# TO-56_Laser_Simple_4_Pin_Mount.net
KiCad netlist of a schematic drawn in EasyEDA Pro
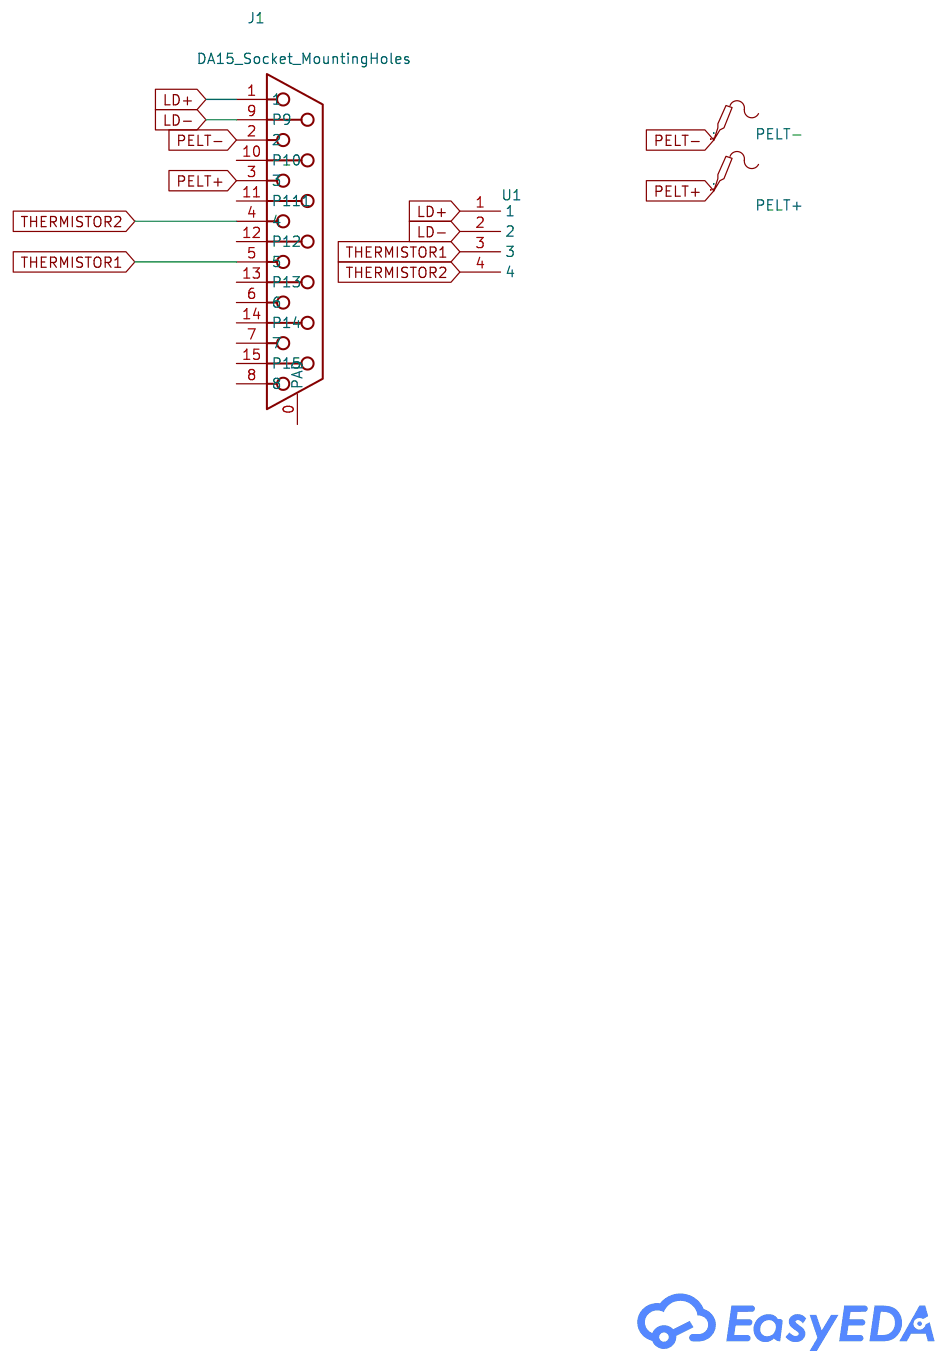
[diagram p0: schematic sheet]

(export (version "E")
  (design (tool "Eeschema 10.0.6"))
  (components
    (comp (ref "J1")
      (value "DA15_Socket_MountingHoles")
      (footprint "easyedapro:Connector_Dsub:DSUB-15_Socket_Vertical_P2.77x2.84mm_MountingHoles")
      (description "15-pin D-SUB connector, socket (female) (low-density/2 columns), Mounting Hole")
      (libsource (lib "easyedapro") (part "Connector_DA15_Socket_MountingHoles"))
    )
    (comp (ref "PELT+")
      (value "~")
      (footprint "easyedapro:Test-Point-0.5mm")
      (description "Test-Point")
      (libsource (lib "easyedapro") (part "Test-Point"))
    )
    (comp (ref "PELT-")
      (value "~")
      (footprint "easyedapro:Test-Point-0.5mm")
      (description "Test-Point")
      (libsource (lib "easyedapro") (part "Test-Point"))
    )
    (comp (ref "U1") (value "~") (footprint "easyedapro:TO56") (libsource (lib "easyedapro") (part "TO56")))
  )
  (nets
    (net (code "1") (name "LD+") (class "Default")
      (node (ref "J1") (pin "1") (pinfunction "1_1") (pintype "unspecified"))
      (node (ref "U1") (pin "1") (pinfunction "1_1") (pintype "input"))
    )
    (net (code "2") (name "LD-") (class "Default")
      (node (ref "J1") (pin "9") (pinfunction "P9_9") (pintype "unspecified"))
      (node (ref "U1") (pin "2") (pinfunction "2_2") (pintype "input"))
    )
    (net (code "3") (name "PELT+") (class "Default")
      (node (ref "J1") (pin "3") (pinfunction "3_3") (pintype "unspecified"))
      (node (ref "PELT+") (pin "1") (pinfunction "1_1") (pintype "input"))
    )
    (net (code "4") (name "PELT-") (class "Default")
      (node (ref "J1") (pin "2") (pinfunction "2_2") (pintype "unspecified"))
      (node (ref "PELT-") (pin "1") (pinfunction "1_1") (pintype "input"))
    )
    (net (code "5") (name "THERMISTOR1") (class "Default")
      (node (ref "J1") (pin "5") (pinfunction "5_5") (pintype "unspecified"))
      (node (ref "U1") (pin "3") (pinfunction "3_3") (pintype "input"))
    )
    (net (code "6") (name "THERMISTOR2") (class "Default")
      (node (ref "J1") (pin "4") (pinfunction "4_4") (pintype "unspecified"))
      (node (ref "U1") (pin "4") (pinfunction "4_4") (pintype "input"))
    )
    (net (code "7") (name "unconnected-(J1-P10-Pad10)") (class "Default")
      (node (ref "J1") (pin "10") (pinfunction "P10_10") (pintype "unspecified"))
    )
    (net (code "8") (name "unconnected-(J1-P12-Pad12)") (class "Default")
      (node (ref "J1") (pin "12") (pinfunction "P12_12") (pintype "unspecified"))
    )
    (net (code "9") (name "unconnected-(J1-P13-Pad13)") (class "Default")
      (node (ref "J1") (pin "13") (pinfunction "P13_13") (pintype "unspecified"))
    )
    (net (code "10") (name "unconnected-(J1-P14-Pad14)") (class "Default")
      (node (ref "J1") (pin "14") (pinfunction "P14_14") (pintype "unspecified"))
    )
    (net (code "11") (name "unconnected-(J1-P15-Pad15)") (class "Default")
      (node (ref "J1") (pin "15") (pinfunction "P15_15") (pintype "unspecified"))
    )
    (net (code "12") (name "unconnected-(J1-P111-Pad11)") (class "Default")
      (node (ref "J1") (pin "11") (pinfunction "P111_11") (pintype "unspecified"))
    )
    (net (code "13") (name "unconnected-(J1-PAD-Pad0)") (class "Default")
      (node (ref "J1") (pin "0") (pinfunction "PAD_0") (pintype "unspecified"))
    )
    (net (code "14") (name "unconnected-(J1-Pad6)") (class "Default")
      (node (ref "J1") (pin "6") (pinfunction "6_6") (pintype "unspecified"))
    )
    (net (code "15") (name "unconnected-(J1-Pad7)") (class "Default")
      (node (ref "J1") (pin "7") (pinfunction "7_7") (pintype "unspecified"))
    )
    (net (code "16") (name "unconnected-(J1-Pad8)") (class "Default")
      (node (ref "J1") (pin "8") (pinfunction "8_8") (pintype "unspecified"))
    )
  )
)
